# vme_can_vme_1.net
KiCad netlist of a schematic drawn in Altium Designer
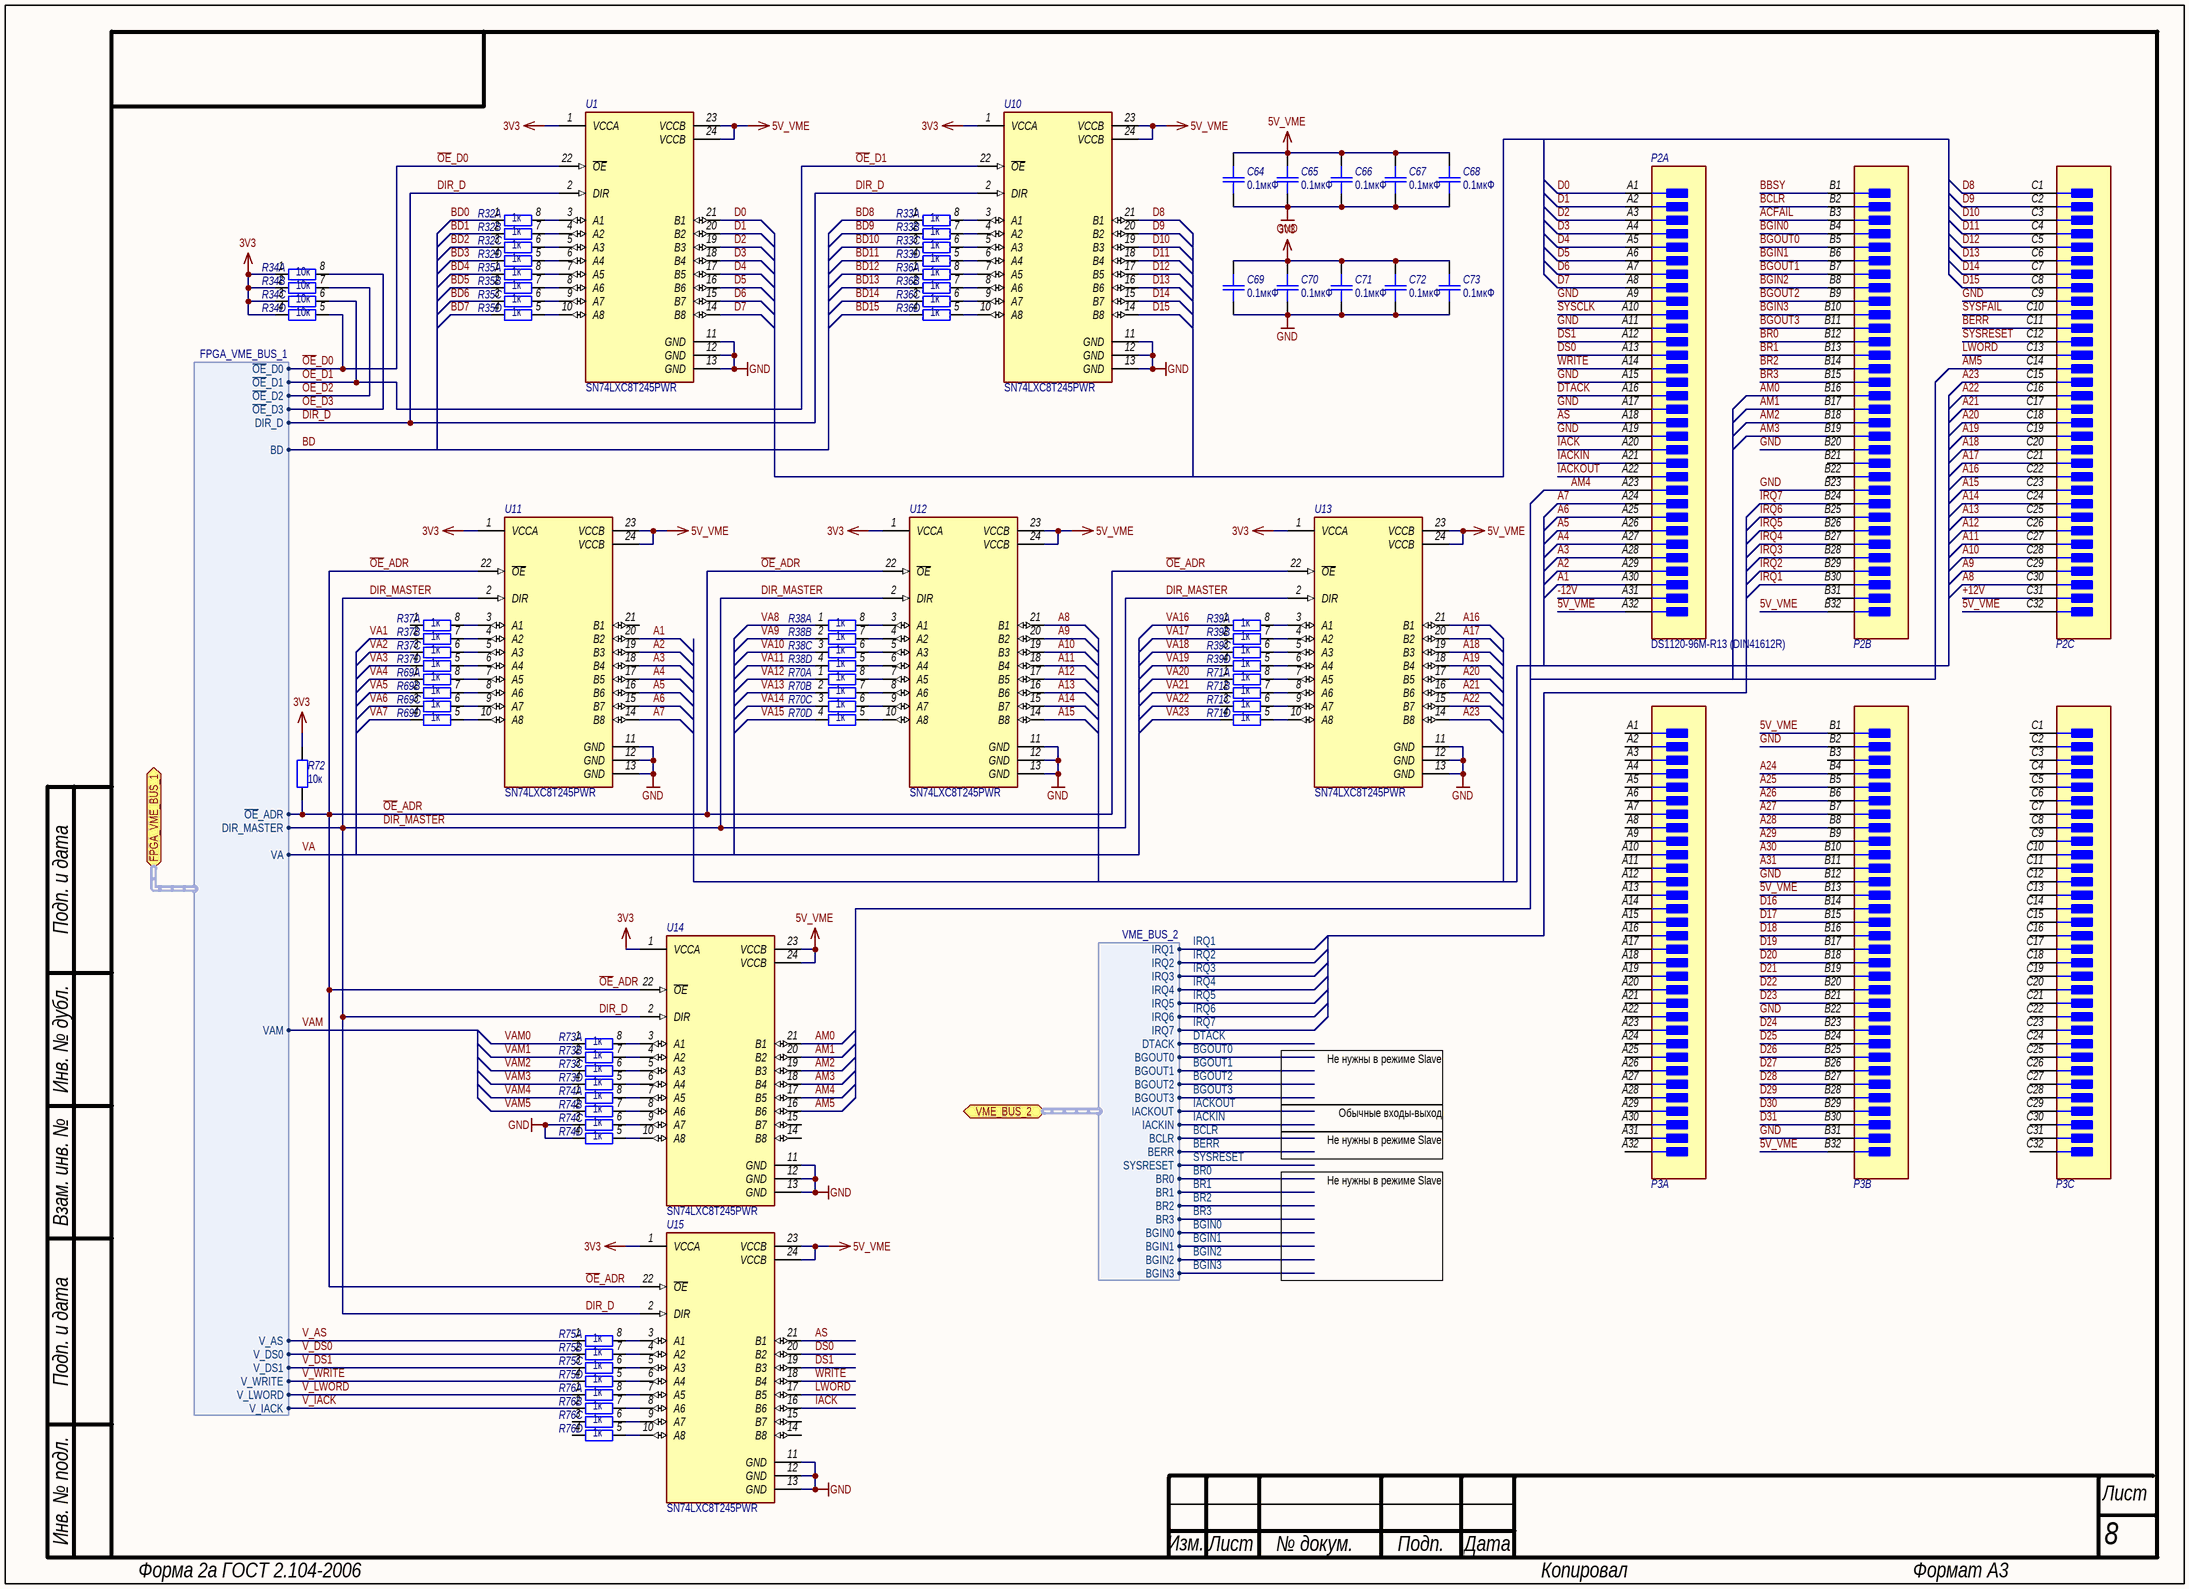
[diagram p0: vme_can_vme_1.SchDoc]

(export (version "E")
  (design (tool "Eeschema 10.0.6"))
  (components
    (comp (ref "C64")
      (value "0.1мкФ")
      (footprint "SMD_C0805")
      (description "Capacitor")
      (libsource (lib "Passive") (part "Capacitor"))
    )
    (comp (ref "C65")
      (value "0.1мкФ")
      (footprint "SMD_C0805")
      (description "Capacitor")
      (libsource (lib "Passive") (part "Capacitor"))
    )
    (comp (ref "C66")
      (value "0.1мкФ")
      (footprint "SMD_C0805")
      (description "Capacitor")
      (libsource (lib "Passive") (part "Capacitor"))
    )
    (comp (ref "C67")
      (value "0.1мкФ")
      (footprint "SMD_C0805")
      (description "Capacitor")
      (libsource (lib "Passive") (part "Capacitor"))
    )
    (comp (ref "C68")
      (value "0.1мкФ")
      (footprint "SMD_C0805")
      (description "Capacitor")
      (libsource (lib "Passive") (part "Capacitor"))
    )
    (comp (ref "C69")
      (value "0.1мкФ")
      (footprint "SMD_C0805")
      (description "Capacitor")
      (libsource (lib "Passive") (part "Capacitor"))
    )
    (comp (ref "C70")
      (value "0.1мкФ")
      (footprint "SMD_C0805")
      (description "Capacitor")
      (libsource (lib "Passive") (part "Capacitor"))
    )
    (comp (ref "C71")
      (value "0.1мкФ")
      (footprint "SMD_C0805")
      (description "Capacitor")
      (libsource (lib "Passive") (part "Capacitor"))
    )
    (comp (ref "C72")
      (value "0.1мкФ")
      (footprint "SMD_C0805")
      (description "Capacitor")
      (libsource (lib "Passive") (part "Capacitor"))
    )
    (comp (ref "C73")
      (value "0.1мкФ")
      (footprint "SMD_C0805")
      (description "Capacitor")
      (libsource (lib "Passive") (part "Capacitor"))
    )
    (comp (ref "P2")
      (value "DS1120-96M-R13 (DIN41612R)")
      (footprint "DS1120-96M-R13")
      (description "Conn Backplane PL 96 POS 2.54mm Solder RA Thru-Hole Box")
      (fields
        (field (name "MANUFACTURER") "TE")
        (field (name "OCTOPART") "https://octopart.com/5650473-5-te+connectivity-39687507")
        (field (name "НАИМЕНОВАНИЕ") "DS1120-96M-R13 (DIN41612R)")
      )
      (libsource (lib "Connector") (part "DS1120-96M-R13"))
    )
    (comp (ref "P3")
      (value "DS1120-96M-R13 (DIN41612R)")
      (footprint "DS1120-96M-R13")
      (description "Conn Backplane PL 96 POS 2.54mm Solder RA Thru-Hole Box")
      (fields
        (field (name "MANUFACTURER") "TE")
        (field (name "OCTOPART") "https://octopart.com/5650473-5-te+connectivity-39687507")
      )
      (libsource (lib "Connector") (part "DS1120-96M-R13"))
    )
    (comp (ref "R32")
      (value "1к")
      (footprint "TC124")
      (description "4 Chip Resistor Array")
      (libsource (lib "Passive") (part "Resistor-4"))
    )
    (comp (ref "R33")
      (value "1к")
      (footprint "TC124")
      (description "4 Chip Resistor Array")
      (libsource (lib "Passive") (part "Resistor-4"))
    )
    (comp (ref "R34")
      (value "10к")
      (footprint "TC124")
      (description "4 Chip Resistor Array")
      (libsource (lib "Passive") (part "Resistor-4"))
    )
    (comp (ref "R35")
      (value "1к")
      (footprint "TC124")
      (description "4 Chip Resistor Array")
      (libsource (lib "Passive") (part "Resistor-4"))
    )
    (comp (ref "R36")
      (value "1к")
      (footprint "TC124")
      (description "4 Chip Resistor Array")
      (libsource (lib "Passive") (part "Resistor-4"))
    )
    (comp (ref "R37")
      (value "1к")
      (footprint "TC124")
      (description "4 Chip Resistor Array")
      (libsource (lib "Passive") (part "Resistor-4"))
    )
    (comp (ref "R38")
      (value "1к")
      (footprint "TC124")
      (description "4 Chip Resistor Array")
      (libsource (lib "Passive") (part "Resistor-4"))
    )
    (comp (ref "R39")
      (value "1к")
      (footprint "TC124")
      (description "4 Chip Resistor Array")
      (libsource (lib "Passive") (part "Resistor-4"))
    )
    (comp (ref "R69")
      (value "1к")
      (footprint "TC124")
      (description "4 Chip Resistor Array")
      (libsource (lib "Passive") (part "Resistor-4"))
    )
    (comp (ref "R70")
      (value "1к")
      (footprint "TC124")
      (description "4 Chip Resistor Array")
      (libsource (lib "Passive") (part "Resistor-4"))
    )
    (comp (ref "R71")
      (value "1к")
      (footprint "TC124")
      (description "4 Chip Resistor Array")
      (libsource (lib "Passive") (part "Resistor-4"))
    )
    (comp (ref "R72")
      (value "10к")
      (footprint "SMD_0805")
      (description "Resistor")
      (libsource (lib "Passive") (part "Resistor"))
    )
    (comp (ref "R73")
      (value "1к")
      (footprint "TC124")
      (description "4 Chip Resistor Array")
      (libsource (lib "Passive") (part "Resistor-4"))
    )
    (comp (ref "R74")
      (value "1к")
      (footprint "TC124")
      (description "4 Chip Resistor Array")
      (libsource (lib "Passive") (part "Resistor-4"))
    )
    (comp (ref "R75")
      (value "1к")
      (footprint "TC124")
      (description "4 Chip Resistor Array")
      (libsource (lib "Passive") (part "Resistor-4"))
    )
    (comp (ref "R76")
      (value "1к")
      (footprint "TC124")
      (description "4 Chip Resistor Array")
      (libsource (lib "Passive") (part "Resistor-4"))
    )
    (comp (ref "U1")
      (value "SN74LXC8T245PWR")
      (footprint "TSSOP-24")
      (description "Dual-Supply Bus Transceiver with Configurable Level Shifting\r\nand 3-State Outputs")
      (fields (field (name "НАИМЕНОВАНИЕ") "SN74LXC8T245PWR"))
      (libsource (lib "Transceiver") (part "SN74LXC8T245PWR"))
    )
    (comp (ref "U10")
      (value "SN74LXC8T245PWR")
      (footprint "TSSOP-24")
      (description "Dual-Supply Bus Transceiver with Configurable Level Shifting\r\nand 3-State Outputs")
      (fields (field (name "НАИМЕНОВАНИЕ") "SN74LXC8T245PWR"))
      (libsource (lib "Transceiver") (part "SN74LXC8T245PWR"))
    )
    (comp (ref "U11")
      (value "SN74LXC8T245PWR")
      (footprint "TSSOP-24")
      (description "Dual-Supply Bus Transceiver with Configurable Level Shifting\r\nand 3-State Outputs")
      (fields (field (name "НАИМЕНОВАНИЕ") "SN74LXC8T245PWR"))
      (libsource (lib "Transceiver") (part "SN74LXC8T245PWR"))
    )
    (comp (ref "U12")
      (value "SN74LXC8T245PWR")
      (footprint "TSSOP-24")
      (description "Dual-Supply Bus Transceiver with Configurable Level Shifting\r\nand 3-State Outputs")
      (fields (field (name "НАИМЕНОВАНИЕ") "SN74LXC8T245PWR"))
      (libsource (lib "Transceiver") (part "SN74LXC8T245PWR"))
    )
    (comp (ref "U13")
      (value "SN74LXC8T245PWR")
      (footprint "TSSOP-24")
      (description "Dual-Supply Bus Transceiver with Configurable Level Shifting\r\nand 3-State Outputs")
      (fields (field (name "НАИМЕНОВАНИЕ") "SN74LXC8T245PWR"))
      (libsource (lib "Transceiver") (part "SN74LXC8T245PWR"))
    )
    (comp (ref "U14")
      (value "SN74LXC8T245PWR")
      (footprint "TSSOP-24")
      (description "Dual-Supply Bus Transceiver with Configurable Level Shifting\r\nand 3-State Outputs")
      (fields (field (name "НАИМЕНОВАНИЕ") "SN74LXC8T245PWR"))
      (libsource (lib "Transceiver") (part "SN74LXC8T245PWR"))
    )
    (comp (ref "U15")
      (value "SN74LXC8T245PWR")
      (footprint "TSSOP-24")
      (description "Dual-Supply Bus Transceiver with Configurable Level Shifting\r\nand 3-State Outputs")
      (fields (field (name "НАИМЕНОВАНИЕ") "SN74LXC8T245PWR"))
      (libsource (lib "Transceiver") (part "SN74LXC8T245PWR"))
    )
  )
  (nets
    (net (code "6") (name "/+12V") (class "Default")
      (node (ref "P2") (pin "C31") (pinfunction "C31_C31") (pintype "passive"))
    )
    (net (code "7") (name "/-12V") (class "Default")
      (node (ref "P2") (pin "A31") (pinfunction "A31_A31") (pintype "passive"))
    )
    (net (code "8") (name "/A1") (class "Default")
      (node (ref "P2") (pin "A30") (pinfunction "A30_A30") (pintype "passive"))
      (node (ref "U11") (pin "20") (pinfunction "B2_20") (pintype "bidirectional"))
    )
    (net (code "9") (name "/A2") (class "Default")
      (node (ref "P2") (pin "A29") (pinfunction "A29_A29") (pintype "passive"))
      (node (ref "U11") (pin "19") (pinfunction "B3_19") (pintype "bidirectional"))
    )
    (net (code "10") (name "/A3") (class "Default")
      (node (ref "P2") (pin "A28") (pinfunction "A28_A28") (pintype "passive"))
      (node (ref "U11") (pin "18") (pinfunction "B4_18") (pintype "bidirectional"))
    )
    (net (code "11") (name "/A4") (class "Default")
      (node (ref "P2") (pin "A27") (pinfunction "A27_A27") (pintype "passive"))
      (node (ref "U11") (pin "17") (pinfunction "B5_17") (pintype "bidirectional"))
    )
    (net (code "12") (name "/A5") (class "Default")
      (node (ref "P2") (pin "A26") (pinfunction "A26_A26") (pintype "passive"))
      (node (ref "U11") (pin "16") (pinfunction "B6_16") (pintype "bidirectional"))
    )
    (net (code "13") (name "/A6") (class "Default")
      (node (ref "P2") (pin "A25") (pinfunction "A25_A25") (pintype "passive"))
      (node (ref "U11") (pin "15") (pinfunction "B7_15") (pintype "bidirectional"))
    )
    (net (code "14") (name "/A7") (class "Default")
      (node (ref "P2") (pin "A24") (pinfunction "A24_A24") (pintype "passive"))
      (node (ref "U11") (pin "14") (pinfunction "B8_14") (pintype "bidirectional"))
    )
    (net (code "15") (name "/A8") (class "Default")
      (node (ref "P2") (pin "C30") (pinfunction "C30_C30") (pintype "passive"))
      (node (ref "U12") (pin "21") (pinfunction "B1_21") (pintype "bidirectional"))
    )
    (net (code "16") (name "/A9") (class "Default")
      (node (ref "P2") (pin "C29") (pinfunction "C29_C29") (pintype "passive"))
      (node (ref "U12") (pin "20") (pinfunction "B2_20") (pintype "bidirectional"))
    )
    (net (code "17") (name "/A10") (class "Default")
      (node (ref "P2") (pin "C28") (pinfunction "C28_C28") (pintype "passive"))
      (node (ref "U12") (pin "19") (pinfunction "B3_19") (pintype "bidirectional"))
    )
    (net (code "18") (name "/A11") (class "Default")
      (node (ref "P2") (pin "C27") (pinfunction "C27_C27") (pintype "passive"))
      (node (ref "U12") (pin "18") (pinfunction "B4_18") (pintype "bidirectional"))
    )
    (net (code "19") (name "/A12") (class "Default")
      (node (ref "P2") (pin "C26") (pinfunction "C26_C26") (pintype "passive"))
      (node (ref "U12") (pin "17") (pinfunction "B5_17") (pintype "bidirectional"))
    )
    (net (code "20") (name "/A13") (class "Default")
      (node (ref "P2") (pin "C25") (pinfunction "C25_C25") (pintype "passive"))
      (node (ref "U12") (pin "16") (pinfunction "B6_16") (pintype "bidirectional"))
    )
    (net (code "21") (name "/A14") (class "Default")
      (node (ref "P2") (pin "C24") (pinfunction "C24_C24") (pintype "passive"))
      (node (ref "U12") (pin "15") (pinfunction "B7_15") (pintype "bidirectional"))
    )
    (net (code "22") (name "/A15") (class "Default")
      (node (ref "P2") (pin "C23") (pinfunction "C23_C23") (pintype "passive"))
      (node (ref "U12") (pin "14") (pinfunction "B8_14") (pintype "bidirectional"))
    )
    (net (code "23") (name "/A16") (class "Default")
      (node (ref "P2") (pin "C22") (pinfunction "C22_C22") (pintype "passive"))
      (node (ref "U13") (pin "21") (pinfunction "B1_21") (pintype "bidirectional"))
    )
    (net (code "24") (name "/A17") (class "Default")
      (node (ref "P2") (pin "C21") (pinfunction "C21_C21") (pintype "passive"))
      (node (ref "U13") (pin "20") (pinfunction "B2_20") (pintype "bidirectional"))
    )
    (net (code "25") (name "/A18") (class "Default")
      (node (ref "P2") (pin "C20") (pinfunction "C20_C20") (pintype "passive"))
      (node (ref "U13") (pin "19") (pinfunction "B3_19") (pintype "bidirectional"))
    )
    (net (code "26") (name "/A19") (class "Default")
      (node (ref "P2") (pin "C19") (pinfunction "C19_C19") (pintype "passive"))
      (node (ref "U13") (pin "18") (pinfunction "B4_18") (pintype "bidirectional"))
    )
    (net (code "27") (name "/A20") (class "Default")
      (node (ref "P2") (pin "C18") (pinfunction "C18_C18") (pintype "passive"))
      (node (ref "U13") (pin "17") (pinfunction "B5_17") (pintype "bidirectional"))
    )
    (net (code "28") (name "/A21") (class "Default")
      (node (ref "P2") (pin "C17") (pinfunction "C17_C17") (pintype "passive"))
      (node (ref "U13") (pin "16") (pinfunction "B6_16") (pintype "bidirectional"))
    )
    (net (code "29") (name "/A22") (class "Default")
      (node (ref "P2") (pin "C16") (pinfunction "C16_C16") (pintype "passive"))
      (node (ref "U13") (pin "15") (pinfunction "B7_15") (pintype "bidirectional"))
    )
    (net (code "30") (name "/A23") (class "Default")
      (node (ref "P2") (pin "C15") (pinfunction "C15_C15") (pintype "passive"))
      (node (ref "U13") (pin "14") (pinfunction "B8_14") (pintype "bidirectional"))
    )
    (net (code "31") (name "/A24") (class "Default")
      (node (ref "P3") (pin "B4") (pinfunction "B4_B4") (pintype "passive"))
    )
    (net (code "32") (name "/A25") (class "Default")
      (node (ref "P3") (pin "B5") (pinfunction "B5_B5") (pintype "passive"))
    )
    (net (code "33") (name "/A26") (class "Default")
      (node (ref "P3") (pin "B6") (pinfunction "B6_B6") (pintype "passive"))
    )
    (net (code "34") (name "/A27") (class "Default")
      (node (ref "P3") (pin "B7") (pinfunction "B7_B7") (pintype "passive"))
    )
    (net (code "35") (name "/A28") (class "Default")
      (node (ref "P3") (pin "B8") (pinfunction "B8_B8") (pintype "passive"))
    )
    (net (code "36") (name "/A29") (class "Default")
      (node (ref "P3") (pin "B9") (pinfunction "B9_B9") (pintype "passive"))
    )
    (net (code "37") (name "/A30") (class "Default")
      (node (ref "P3") (pin "B10") (pinfunction "B10_B10") (pintype "passive"))
    )
    (net (code "38") (name "/A31") (class "Default")
      (node (ref "P3") (pin "B11") (pinfunction "B11_B11") (pintype "passive"))
    )
    (net (code "39") (name "/ACFAIL") (class "Default")
      (node (ref "P2") (pin "B3") (pinfunction "B3_B3") (pintype "passive"))
    )
    (net (code "40") (name "/AM0") (class "Default")
      (node (ref "P2") (pin "B16") (pinfunction "B16_B16") (pintype "passive"))
      (node (ref "U14") (pin "21") (pinfunction "B1_21") (pintype "bidirectional"))
    )
    (net (code "41") (name "/AM1") (class "Default")
      (node (ref "P2") (pin "B17") (pinfunction "B17_B17") (pintype "passive"))
      (node (ref "U14") (pin "20") (pinfunction "B2_20") (pintype "bidirectional"))
    )
    (net (code "42") (name "/AM2") (class "Default")
      (node (ref "P2") (pin "B18") (pinfunction "B18_B18") (pintype "passive"))
      (node (ref "U14") (pin "19") (pinfunction "B3_19") (pintype "bidirectional"))
    )
    (net (code "43") (name "/AM3") (class "Default")
      (node (ref "P2") (pin "B19") (pinfunction "B19_B19") (pintype "passive"))
      (node (ref "U14") (pin "18") (pinfunction "B4_18") (pintype "bidirectional"))
    )
    (net (code "44") (name "/AM4") (class "Default")
      (node (ref "P2") (pin "A23") (pinfunction "A23_A23") (pintype "passive"))
      (node (ref "U14") (pin "17") (pinfunction "B5_17") (pintype "bidirectional"))
    )
    (net (code "45") (name "/AM5") (class "Default")
      (node (ref "P2") (pin "C14") (pinfunction "C14_C14") (pintype "passive"))
      (node (ref "U14") (pin "16") (pinfunction "B6_16") (pintype "bidirectional"))
    )
    (net (code "46") (name "/AS") (class "Default")
      (node (ref "P2") (pin "A18") (pinfunction "A18_A18") (pintype "passive"))
      (node (ref "U15") (pin "21") (pinfunction "B1_21") (pintype "bidirectional"))
    )
    (net (code "47") (name "/BBSY") (class "Default")
      (node (ref "P2") (pin "B1") (pinfunction "B1_B1") (pintype "passive"))
    )
    (net (code "48") (name "/BCLR") (class "Default")
      (node (ref "P2") (pin "B2") (pinfunction "B2_B2") (pintype "passive"))
    )
    (net (code "49") (name "/BD0") (class "Default")
      (node (ref "R32") (pin "1") (pinfunction "1_1") (pintype "passive"))
    )
    (net (code "50") (name "/BD1") (class "Default")
      (node (ref "R32") (pin "2") (pinfunction "2_2") (pintype "passive"))
    )
    (net (code "51") (name "/BD2") (class "Default")
      (node (ref "R32") (pin "3") (pinfunction "3_3") (pintype "passive"))
    )
    (net (code "52") (name "/BD3") (class "Default")
      (node (ref "R32") (pin "4") (pinfunction "4_4") (pintype "passive"))
    )
    (net (code "53") (name "/BD4") (class "Default")
      (node (ref "R35") (pin "1") (pinfunction "1_1") (pintype "passive"))
    )
    (net (code "54") (name "/BD5") (class "Default")
      (node (ref "R35") (pin "2") (pinfunction "2_2") (pintype "passive"))
    )
    (net (code "55") (name "/BD6") (class "Default")
      (node (ref "R35") (pin "3") (pinfunction "3_3") (pintype "passive"))
    )
    (net (code "56") (name "/BD7") (class "Default")
      (node (ref "R35") (pin "4") (pinfunction "4_4") (pintype "passive"))
    )
    (net (code "57") (name "/BD8") (class "Default")
      (node (ref "R33") (pin "1") (pinfunction "1_1") (pintype "passive"))
    )
    (net (code "58") (name "/BD9") (class "Default")
      (node (ref "R33") (pin "2") (pinfunction "2_2") (pintype "passive"))
    )
    (net (code "59") (name "/BD10") (class "Default")
      (node (ref "R33") (pin "3") (pinfunction "3_3") (pintype "passive"))
    )
    (net (code "60") (name "/BD11") (class "Default")
      (node (ref "R33") (pin "4") (pinfunction "4_4") (pintype "passive"))
    )
    (net (code "61") (name "/BD12") (class "Default")
      (node (ref "R36") (pin "1") (pinfunction "1_1") (pintype "passive"))
    )
    (net (code "62") (name "/BD13") (class "Default")
      (node (ref "R36") (pin "2") (pinfunction "2_2") (pintype "passive"))
    )
    (net (code "63") (name "/BD14") (class "Default")
      (node (ref "R36") (pin "3") (pinfunction "3_3") (pintype "passive"))
    )
    (net (code "64") (name "/BD15") (class "Default")
      (node (ref "R36") (pin "4") (pinfunction "4_4") (pintype "passive"))
    )
    (net (code "65") (name "/BERR") (class "Default")
      (node (ref "P2") (pin "C11") (pinfunction "C11_C11") (pintype "passive"))
    )
    (net (code "66") (name "/BGIN0") (class "Default")
      (node (ref "P2") (pin "B4") (pinfunction "B4_B4") (pintype "passive"))
    )
    (net (code "67") (name "/BGIN1") (class "Default")
      (node (ref "P2") (pin "B6") (pinfunction "B6_B6") (pintype "passive"))
    )
    (net (code "68") (name "/BGIN2") (class "Default")
      (node (ref "P2") (pin "B8") (pinfunction "B8_B8") (pintype "passive"))
    )
    (net (code "69") (name "/BGIN3") (class "Default")
      (node (ref "P2") (pin "B10") (pinfunction "B10_B10") (pintype "passive"))
    )
    (net (code "70") (name "/BGOUT0") (class "Default")
      (node (ref "P2") (pin "B5") (pinfunction "B5_B5") (pintype "passive"))
    )
    (net (code "71") (name "/BGOUT1") (class "Default")
      (node (ref "P2") (pin "B7") (pinfunction "B7_B7") (pintype "passive"))
    )
    (net (code "72") (name "/BGOUT2") (class "Default")
      (node (ref "P2") (pin "B9") (pinfunction "B9_B9") (pintype "passive"))
    )
    (net (code "73") (name "/BGOUT3") (class "Default")
      (node (ref "P2") (pin "B11") (pinfunction "B11_B11") (pintype "passive"))
    )
    (net (code "74") (name "/BR0") (class "Default")
      (node (ref "P2") (pin "B12") (pinfunction "B12_B12") (pintype "passive"))
    )
    (net (code "75") (name "/BR1") (class "Default")
      (node (ref "P2") (pin "B13") (pinfunction "B13_B13") (pintype "passive"))
    )
    (net (code "76") (name "/BR2") (class "Default")
      (node (ref "P2") (pin "B14") (pinfunction "B14_B14") (pintype "passive"))
    )
    (net (code "77") (name "/BR3") (class "Default")
      (node (ref "P2") (pin "B15") (pinfunction "B15_B15") (pintype "passive"))
    )
    (net (code "78") (name "/D0") (class "Default")
      (node (ref "P2") (pin "A1") (pinfunction "A1_A1") (pintype "passive"))
      (node (ref "U1") (pin "21") (pinfunction "B1_21") (pintype "bidirectional"))
    )
    (net (code "79") (name "/D1") (class "Default")
      (node (ref "P2") (pin "A2") (pinfunction "A2_A2") (pintype "passive"))
      (node (ref "U1") (pin "20") (pinfunction "B2_20") (pintype "bidirectional"))
    )
    (net (code "80") (name "/D2") (class "Default")
      (node (ref "P2") (pin "A3") (pinfunction "A3_A3") (pintype "passive"))
      (node (ref "U1") (pin "19") (pinfunction "B3_19") (pintype "bidirectional"))
    )
    (net (code "81") (name "/D3") (class "Default")
      (node (ref "P2") (pin "A4") (pinfunction "A4_A4") (pintype "passive"))
      (node (ref "U1") (pin "18") (pinfunction "B4_18") (pintype "bidirectional"))
    )
    (net (code "82") (name "/D4") (class "Default")
      (node (ref "P2") (pin "A5") (pinfunction "A5_A5") (pintype "passive"))
      (node (ref "U1") (pin "17") (pinfunction "B5_17") (pintype "bidirectional"))
    )
    (net (code "83") (name "/D5") (class "Default")
      (node (ref "P2") (pin "A6") (pinfunction "A6_A6") (pintype "passive"))
      (node (ref "U1") (pin "16") (pinfunction "B6_16") (pintype "bidirectional"))
    )
    (net (code "84") (name "/D6") (class "Default")
      (node (ref "P2") (pin "A7") (pinfunction "A7_A7") (pintype "passive"))
      (node (ref "U1") (pin "15") (pinfunction "B7_15") (pintype "bidirectional"))
    )
    (net (code "85") (name "/D7") (class "Default")
      (node (ref "P2") (pin "A8") (pinfunction "A8_A8") (pintype "passive"))
      (node (ref "U1") (pin "14") (pinfunction "B8_14") (pintype "bidirectional"))
    )
    (net (code "86") (name "/D8") (class "Default")
      (node (ref "P2") (pin "C1") (pinfunction "C1_C1") (pintype "passive"))
      (node (ref "U10") (pin "21") (pinfunction "B1_21") (pintype "bidirectional"))
    )
    (net (code "87") (name "/D9") (class "Default")
      (node (ref "P2") (pin "C2") (pinfunction "C2_C2") (pintype "passive"))
      (node (ref "U10") (pin "20") (pinfunction "B2_20") (pintype "bidirectional"))
    )
    (net (code "88") (name "/D10") (class "Default")
      (node (ref "P2") (pin "C3") (pinfunction "C3_C3") (pintype "passive"))
      (node (ref "U10") (pin "19") (pinfunction "B3_19") (pintype "bidirectional"))
    )
    (net (code "89") (name "/D11") (class "Default")
      (node (ref "P2") (pin "C4") (pinfunction "C4_C4") (pintype "passive"))
      (node (ref "U10") (pin "18") (pinfunction "B4_18") (pintype "bidirectional"))
    )
    (net (code "90") (name "/D12") (class "Default")
      (node (ref "P2") (pin "C5") (pinfunction "C5_C5") (pintype "passive"))
      (node (ref "U10") (pin "17") (pinfunction "B5_17") (pintype "bidirectional"))
    )
    (net (code "91") (name "/D13") (class "Default")
      (node (ref "P2") (pin "C6") (pinfunction "C6_C6") (pintype "passive"))
      (node (ref "U10") (pin "16") (pinfunction "B6_16") (pintype "bidirectional"))
    )
    (net (code "92") (name "/D14") (class "Default")
      (node (ref "P2") (pin "C7") (pinfunction "C7_C7") (pintype "passive"))
      (node (ref "U10") (pin "15") (pinfunction "B7_15") (pintype "bidirectional"))
    )
    (net (code "93") (name "/D15") (class "Default")
      (node (ref "P2") (pin "C8") (pinfunction "C8_C8") (pintype "passive"))
      (node (ref "U10") (pin "14") (pinfunction "B8_14") (pintype "bidirectional"))
    )
    (net (code "94") (name "/D16") (class "Default")
      (node (ref "P3") (pin "B14") (pinfunction "B14_B14") (pintype "passive"))
    )
    (net (code "95") (name "/D17") (class "Default")
      (node (ref "P3") (pin "B15") (pinfunction "B15_B15") (pintype "passive"))
    )
    (net (code "96") (name "/D18") (class "Default")
      (node (ref "P3") (pin "B16") (pinfunction "B16_B16") (pintype "passive"))
    )
    (net (code "97") (name "/D19") (class "Default")
      (node (ref "P3") (pin "B17") (pinfunction "B17_B17") (pintype "passive"))
    )
    (net (code "98") (name "/D20") (class "Default")
      (node (ref "P3") (pin "B18") (pinfunction "B18_B18") (pintype "passive"))
    )
    (net (code "99") (name "/D21") (class "Default")
      (node (ref "P3") (pin "B19") (pinfunction "B19_B19") (pintype "passive"))
    )
    (net (code "100") (name "/D22") (class "Default")
      (node (ref "P3") (pin "B20") (pinfunction "B20_B20") (pintype "passive"))
    )
    (net (code "101") (name "/D23") (class "Default")
      (node (ref "P3") (pin "B21") (pinfunction "B21_B21") (pintype "passive"))
    )
    (net (code "102") (name "/D24") (class "Default")
      (node (ref "P3") (pin "B23") (pinfunction "B23_B23") (pintype "passive"))
    )
    (net (code "103") (name "/D25") (class "Default")
      (node (ref "P3") (pin "B24") (pinfunction "B24_B24") (pintype "passive"))
    )
    (net (code "104") (name "/D26") (class "Default")
      (node (ref "P3") (pin "B25") (pinfunction "B25_B25") (pintype "passive"))
    )
    (net (code "105") (name "/D27") (class "Default")
      (node (ref "P3") (pin "B26") (pinfunction "B26_B26") (pintype "passive"))
    )
    (net (code "106") (name "/D28") (class "Default")
      (node (ref "P3") (pin "B27") (pinfunction "B27_B27") (pintype "passive"))
    )
    (net (code "107") (name "/D29") (class "Default")
      (node (ref "P3") (pin "B28") (pinfunction "B28_B28") (pintype "passive"))
    )
    (net (code "108") (name "/D30") (class "Default")
      (node (ref "P3") (pin "B29") (pinfunction "B29_B29") (pintype "passive"))
    )
    (net (code "109") (name "/D31") (class "Default")
      (node (ref "P3") (pin "B30") (pinfunction "B30_B30") (pintype "passive"))
    )
    (net (code "110") (name "/DIR_D") (class "Default")
      (node (ref "U1") (pin "2") (pinfunction "DIR_2") (pintype "input"))
      (node (ref "U10") (pin "2") (pinfunction "DIR_2") (pintype "input"))
      (node (ref "U11") (pin "2") (pinfunction "DIR_2") (pintype "input"))
      (node (ref "U12") (pin "2") (pinfunction "DIR_2") (pintype "input"))
      (node (ref "U13") (pin "2") (pinfunction "DIR_2") (pintype "input"))
      (node (ref "U14") (pin "2") (pinfunction "DIR_2") (pintype "input"))
      (node (ref "U15") (pin "2") (pinfunction "DIR_2") (pintype "input"))
    )
    (net (code "111") (name "/DS0") (class "Default")
      (node (ref "P2") (pin "A13") (pinfunction "A13_A13") (pintype "passive"))
      (node (ref "U15") (pin "20") (pinfunction "B2_20") (pintype "bidirectional"))
    )
    (net (code "112") (name "/DS1") (class "Default")
      (node (ref "P2") (pin "A12") (pinfunction "A12_A12") (pintype "passive"))
      (node (ref "U15") (pin "19") (pinfunction "B3_19") (pintype "bidirectional"))
    )
    (net (code "113") (name "/DTACK") (class "Default")
      (node (ref "P2") (pin "A16") (pinfunction "A16_A16") (pintype "passive"))
    )
    (net (code "115") (name "/IACK") (class "Default")
      (node (ref "P2") (pin "A20") (pinfunction "A20_A20") (pintype "passive"))
      (node (ref "U15") (pin "16") (pinfunction "B6_16") (pintype "bidirectional"))
    )
    (net (code "116") (name "/IACKIN") (class "Default")
      (node (ref "P2") (pin "A21") (pinfunction "A21_A21") (pintype "passive"))
    )
    (net (code "117") (name "/IACKOUT") (class "Default")
      (node (ref "P2") (pin "A22") (pinfunction "A22_A22") (pintype "passive"))
    )
    (net (code "118") (name "/IRQ1") (class "Default")
      (node (ref "P2") (pin "B30") (pinfunction "B30_B30") (pintype "passive"))
    )
    (net (code "119") (name "/IRQ2") (class "Default")
      (node (ref "P2") (pin "B29") (pinfunction "B29_B29") (pintype "passive"))
    )
    (net (code "120") (name "/IRQ3") (class "Default")
      (node (ref "P2") (pin "B28") (pinfunction "B28_B28") (pintype "passive"))
    )
    (net (code "121") (name "/IRQ4") (class "Default")
      (node (ref "P2") (pin "B27") (pinfunction "B27_B27") (pintype "passive"))
    )
    (net (code "122") (name "/IRQ5") (class "Default")
      (node (ref "P2") (pin "B26") (pinfunction "B26_B26") (pintype "passive"))
    )
    (net (code "123") (name "/IRQ6") (class "Default")
      (node (ref "P2") (pin "B25") (pinfunction "B25_B25") (pintype "passive"))
    )
    (net (code "124") (name "/IRQ7") (class "Default")
      (node (ref "P2") (pin "B24") (pinfunction "B24_B24") (pintype "passive"))
    )
    (net (code "125") (name "/LWORD") (class "Default")
      (node (ref "P2") (pin "C13") (pinfunction "C13_C13") (pintype "passive"))
      (node (ref "U15") (pin "17") (pinfunction "B5_17") (pintype "bidirectional"))
    )
    (net (code "126") (name "/SYSCLK") (class "Default")
      (node (ref "P2") (pin "A10") (pinfunction "A10_A10") (pintype "passive"))
    )
    (net (code "127") (name "/SYSFAIL") (class "Default")
      (node (ref "P2") (pin "C10") (pinfunction "C10_C10") (pintype "passive"))
    )
    (net (code "128") (name "/SYSRESET") (class "Default")
      (node (ref "P2") (pin "C12") (pinfunction "C12_C12") (pintype "passive"))
    )
    (net (code "129") (name "/VA1") (class "Default")
      (node (ref "R37") (pin "2") (pinfunction "2_2") (pintype "passive"))
    )
    (net (code "130") (name "/VA2") (class "Default")
      (node (ref "R37") (pin "3") (pinfunction "3_3") (pintype "passive"))
    )
    (net (code "131") (name "/VA3") (class "Default")
      (node (ref "R37") (pin "4") (pinfunction "4_4") (pintype "passive"))
    )
    (net (code "132") (name "/VA4") (class "Default")
      (node (ref "R69") (pin "1") (pinfunction "1_1") (pintype "passive"))
    )
    (net (code "133") (name "/VA5") (class "Default")
      (node (ref "R69") (pin "2") (pinfunction "2_2") (pintype "passive"))
    )
    (net (code "134") (name "/VA6") (class "Default")
      (node (ref "R69") (pin "3") (pinfunction "3_3") (pintype "passive"))
    )
    (net (code "135") (name "/VA7") (class "Default")
      (node (ref "R69") (pin "4") (pinfunction "4_4") (pintype "passive"))
    )
    (net (code "136") (name "/VA8") (class "Default")
      (node (ref "R38") (pin "1") (pinfunction "1_1") (pintype "passive"))
    )
    (net (code "137") (name "/VA9") (class "Default")
      (node (ref "R38") (pin "2") (pinfunction "2_2") (pintype "passive"))
    )
    (net (code "138") (name "/VA10") (class "Default")
      (node (ref "R38") (pin "3") (pinfunction "3_3") (pintype "passive"))
    )
    (net (code "139") (name "/VA11") (class "Default")
      (node (ref "R38") (pin "4") (pinfunction "4_4") (pintype "passive"))
    )
    (net (code "140") (name "/VA12") (class "Default")
      (node (ref "R70") (pin "1") (pinfunction "1_1") (pintype "passive"))
    )
    (net (code "141") (name "/VA13") (class "Default")
      (node (ref "R70") (pin "2") (pinfunction "2_2") (pintype "passive"))
    )
    (net (code "142") (name "/VA14") (class "Default")
      (node (ref "R70") (pin "3") (pinfunction "3_3") (pintype "passive"))
    )
    (net (code "143") (name "/VA15") (class "Default")
      (node (ref "R70") (pin "4") (pinfunction "4_4") (pintype "passive"))
    )
    (net (code "144") (name "/VA16") (class "Default")
      (node (ref "R39") (pin "1") (pinfunction "1_1") (pintype "passive"))
    )
    (net (code "145") (name "/VA17") (class "Default")
      (node (ref "R39") (pin "2") (pinfunction "2_2") (pintype "passive"))
    )
    (net (code "146") (name "/VA18") (class "Default")
      (node (ref "R39") (pin "3") (pinfunction "3_3") (pintype "passive"))
    )
    (net (code "147") (name "/VA19") (class "Default")
      (node (ref "R39") (pin "4") (pinfunction "4_4") (pintype "passive"))
    )
    (net (code "148") (name "/VA20") (class "Default")
      (node (ref "R71") (pin "1") (pinfunction "1_1") (pintype "passive"))
    )
    (net (code "149") (name "/VA21") (class "Default")
      (node (ref "R71") (pin "2") (pinfunction "2_2") (pintype "passive"))
    )
    (net (code "150") (name "/VA22") (class "Default")
      (node (ref "R71") (pin "3") (pinfunction "3_3") (pintype "passive"))
    )
    (net (code "151") (name "/VA23") (class "Default")
      (node (ref "R71") (pin "4") (pinfunction "4_4") (pintype "passive"))
    )
    (net (code "152") (name "/VAM0") (class "Default")
      (node (ref "R73") (pin "1") (pinfunction "1_1") (pintype "passive"))
    )
    (net (code "153") (name "/VAM1") (class "Default")
      (node (ref "R73") (pin "2") (pinfunction "2_2") (pintype "passive"))
    )
    (net (code "154") (name "/VAM2") (class "Default")
      (node (ref "R73") (pin "3") (pinfunction "3_3") (pintype "passive"))
    )
    (net (code "155") (name "/VAM3") (class "Default")
      (node (ref "R73") (pin "4") (pinfunction "4_4") (pintype "passive"))
    )
    (net (code "156") (name "/VAM4") (class "Default")
      (node (ref "R74") (pin "1") (pinfunction "1_1") (pintype "passive"))
    )
    (net (code "157") (name "/VAM5") (class "Default")
      (node (ref "R74") (pin "2") (pinfunction "2_2") (pintype "passive"))
    )
    (net (code "159") (name "/V_AS") (class "Default")
      (node (ref "R75") (pin "1") (pinfunction "1_1") (pintype "passive"))
    )
    (net (code "160") (name "/V_DS0") (class "Default")
      (node (ref "R75") (pin "2") (pinfunction "2_2") (pintype "passive"))
    )
    (net (code "161") (name "/V_DS1") (class "Default")
      (node (ref "R75") (pin "3") (pinfunction "3_3") (pintype "passive"))
    )
    (net (code "162") (name "/V_IACK") (class "Default")
      (node (ref "R76") (pin "2") (pinfunction "2_2") (pintype "passive"))
    )
    (net (code "163") (name "/V_LWORD") (class "Default")
      (node (ref "R76") (pin "1") (pinfunction "1_1") (pintype "passive"))
    )
    (net (code "164") (name "/V_WRITE") (class "Default")
      (node (ref "R75") (pin "4") (pinfunction "4_4") (pintype "passive"))
    )
    (net (code "165") (name "/WRITE") (class "Default")
      (node (ref "P2") (pin "A14") (pinfunction "A14_A14") (pintype "passive"))
      (node (ref "U15") (pin "18") (pinfunction "B4_18") (pintype "bidirectional"))
    )
    (net (code "169") (name "/~{OE}_ADR") (class "Default")
      (node (ref "R72") (pin "1") (pinfunction "1_1") (pintype "passive"))
      (node (ref "U11") (pin "22") (pinfunction "~{OE}_22") (pintype "input"))
      (node (ref "U12") (pin "22") (pinfunction "~{OE}_22") (pintype "input"))
      (node (ref "U13") (pin "22") (pinfunction "~{OE}_22") (pintype "input"))
      (node (ref "U14") (pin "22") (pinfunction "~{OE}_22") (pintype "input"))
      (node (ref "U15") (pin "22") (pinfunction "~{OE}_22") (pintype "input"))
    )
    (net (code "170") (name "/~{OE}_D0") (class "Default")
      (node (ref "R34") (pin "5") (pinfunction "5_5") (pintype "passive"))
      (node (ref "U1") (pin "22") (pinfunction "~{OE}_22") (pintype "input"))
    )
    (net (code "171") (name "/~{OE}_D1") (class "Default")
      (node (ref "R34") (pin "6") (pinfunction "6_6") (pintype "passive"))
      (node (ref "U10") (pin "22") (pinfunction "~{OE}_22") (pintype "input"))
    )
    (net (code "172") (name "/~{OE}_D2") (class "Default")
      (node (ref "R34") (pin "7") (pinfunction "7_7") (pintype "passive"))
    )
    (net (code "173") (name "/~{OE}_D3") (class "Default")
      (node (ref "R34") (pin "8") (pinfunction "8_8") (pintype "passive"))
    )
    (net (code "174") (name "3V3") (class "Default")
      (node (ref "C69") (pin "2") (pinfunction "2_2") (pintype "passive"))
      (node (ref "C70") (pin "2") (pinfunction "2_2") (pintype "passive"))
      (node (ref "C71") (pin "2") (pinfunction "2_2") (pintype "passive"))
      (node (ref "C72") (pin "2") (pinfunction "2_2") (pintype "passive"))
      (node (ref "C73") (pin "2") (pinfunction "2_2") (pintype "passive"))
      (node (ref "R34") (pin "1") (pinfunction "1_1") (pintype "passive"))
      (node (ref "R34") (pin "2") (pinfunction "2_2") (pintype "passive"))
      (node (ref "R34") (pin "3") (pinfunction "3_3") (pintype "passive"))
      (node (ref "R34") (pin "4") (pinfunction "4_4") (pintype "passive"))
      (node (ref "R72") (pin "2") (pinfunction "2_2") (pintype "passive"))
      (node (ref "U1") (pin "1") (pinfunction "VCCA_1") (pintype "power_in"))
      (node (ref "U10") (pin "1") (pinfunction "VCCA_1") (pintype "power_in"))
      (node (ref "U11") (pin "1") (pinfunction "VCCA_1") (pintype "power_in"))
      (node (ref "U12") (pin "1") (pinfunction "VCCA_1") (pintype "power_in"))
      (node (ref "U13") (pin "1") (pinfunction "VCCA_1") (pintype "power_in"))
      (node (ref "U14") (pin "1") (pinfunction "VCCA_1") (pintype "power_in"))
      (node (ref "U15") (pin "1") (pinfunction "VCCA_1") (pintype "power_in"))
    )
    (net (code "175") (name "5V_VME") (class "Default")
      (node (ref "C64") (pin "2") (pinfunction "2_2") (pintype "passive"))
      (node (ref "C65") (pin "2") (pinfunction "2_2") (pintype "passive"))
      (node (ref "C66") (pin "2") (pinfunction "2_2") (pintype "passive"))
      (node (ref "C67") (pin "2") (pinfunction "2_2") (pintype "passive"))
      (node (ref "C68") (pin "2") (pinfunction "2_2") (pintype "passive"))
      (node (ref "P2") (pin "A32") (pinfunction "A32_A32") (pintype "passive"))
      (node (ref "P2") (pin "B32") (pinfunction "B32_B32") (pintype "passive"))
      (node (ref "P2") (pin "C32") (pinfunction "C32_C32") (pintype "passive"))
      (node (ref "P3") (pin "B1") (pinfunction "B1_B1") (pintype "passive"))
      (node (ref "P3") (pin "B13") (pinfunction "B13_B13") (pintype "passive"))
      (node (ref "P3") (pin "B32") (pinfunction "B32_B32") (pintype "passive"))
      (node (ref "U1") (pin "23") (pinfunction "VCCB_23") (pintype "power_in"))
      (node (ref "U1") (pin "24") (pinfunction "VCCB_24") (pintype "power_in"))
      (node (ref "U10") (pin "23") (pinfunction "VCCB_23") (pintype "power_in"))
      (node (ref "U10") (pin "24") (pinfunction "VCCB_24") (pintype "power_in"))
      (node (ref "U11") (pin "23") (pinfunction "VCCB_23") (pintype "power_in"))
      (node (ref "U11") (pin "24") (pinfunction "VCCB_24") (pintype "power_in"))
      (node (ref "U12") (pin "23") (pinfunction "VCCB_23") (pintype "power_in"))
      (node (ref "U12") (pin "24") (pinfunction "VCCB_24") (pintype "power_in"))
      (node (ref "U13") (pin "23") (pinfunction "VCCB_23") (pintype "power_in"))
      (node (ref "U13") (pin "24") (pinfunction "VCCB_24") (pintype "power_in"))
      (node (ref "U14") (pin "23") (pinfunction "VCCB_23") (pintype "power_in"))
      (node (ref "U14") (pin "24") (pinfunction "VCCB_24") (pintype "power_in"))
      (node (ref "U15") (pin "23") (pinfunction "VCCB_23") (pintype "power_in"))
      (node (ref "U15") (pin "24") (pinfunction "VCCB_24") (pintype "power_in"))
    )
    (net (code "176") (name "GND") (class "Default")
      (node (ref "C64") (pin "1") (pinfunction "1_1") (pintype "passive"))
      (node (ref "C65") (pin "1") (pinfunction "1_1") (pintype "passive"))
      (node (ref "C66") (pin "1") (pinfunction "1_1") (pintype "passive"))
      (node (ref "C67") (pin "1") (pinfunction "1_1") (pintype "passive"))
      (node (ref "C68") (pin "1") (pinfunction "1_1") (pintype "passive"))
      (node (ref "C69") (pin "1") (pinfunction "1_1") (pintype "passive"))
      (node (ref "C70") (pin "1") (pinfunction "1_1") (pintype "passive"))
      (node (ref "C71") (pin "1") (pinfunction "1_1") (pintype "passive"))
      (node (ref "C72") (pin "1") (pinfunction "1_1") (pintype "passive"))
      (node (ref "C73") (pin "1") (pinfunction "1_1") (pintype "passive"))
      (node (ref "P2") (pin "A11") (pinfunction "A11_A11") (pintype "passive"))
      (node (ref "P2") (pin "A15") (pinfunction "A15_A15") (pintype "passive"))
      (node (ref "P2") (pin "A17") (pinfunction "A17_A17") (pintype "passive"))
      (node (ref "P2") (pin "A19") (pinfunction "A19_A19") (pintype "passive"))
      (node (ref "P2") (pin "A9") (pinfunction "A9_A9") (pintype "passive"))
      (node (ref "P2") (pin "B20") (pinfunction "B20_B20") (pintype "passive"))
      (node (ref "P2") (pin "B23") (pinfunction "B23_B23") (pintype "passive"))
      (node (ref "P2") (pin "C9") (pinfunction "C9_C9") (pintype "passive"))
      (node (ref "P3") (pin "B12") (pinfunction "B12_B12") (pintype "passive"))
      (node (ref "P3") (pin "B2") (pinfunction "B2_B2") (pintype "passive"))
      (node (ref "P3") (pin "B22") (pinfunction "B22_B22") (pintype "passive"))
      (node (ref "P3") (pin "B31") (pinfunction "B31_B31") (pintype "passive"))
      (node (ref "R74") (pin "3") (pinfunction "3_3") (pintype "passive"))
      (node (ref "R74") (pin "4") (pinfunction "4_4") (pintype "passive"))
      (node (ref "U1") (pin "11") (pinfunction "GND_11") (pintype "power_in"))
      (node (ref "U1") (pin "12") (pinfunction "GND_12") (pintype "power_in"))
      (node (ref "U1") (pin "13") (pinfunction "GND_13") (pintype "power_in"))
      (node (ref "U10") (pin "11") (pinfunction "GND_11") (pintype "power_in"))
      (node (ref "U10") (pin "12") (pinfunction "GND_12") (pintype "power_in"))
      (node (ref "U10") (pin "13") (pinfunction "GND_13") (pintype "power_in"))
      (node (ref "U11") (pin "11") (pinfunction "GND_11") (pintype "power_in"))
      (node (ref "U11") (pin "12") (pinfunction "GND_12") (pintype "power_in"))
      (node (ref "U11") (pin "13") (pinfunction "GND_13") (pintype "power_in"))
      (node (ref "U12") (pin "11") (pinfunction "GND_11") (pintype "power_in"))
      (node (ref "U12") (pin "12") (pinfunction "GND_12") (pintype "power_in"))
      (node (ref "U12") (pin "13") (pinfunction "GND_13") (pintype "power_in"))
      (node (ref "U13") (pin "11") (pinfunction "GND_11") (pintype "power_in"))
      (node (ref "U13") (pin "12") (pinfunction "GND_12") (pintype "power_in"))
      (node (ref "U13") (pin "13") (pinfunction "GND_13") (pintype "power_in"))
      (node (ref "U14") (pin "11") (pinfunction "GND_11") (pintype "power_in"))
      (node (ref "U14") (pin "12") (pinfunction "GND_12") (pintype "power_in"))
      (node (ref "U14") (pin "13") (pinfunction "GND_13") (pintype "power_in"))
      (node (ref "U15") (pin "11") (pinfunction "GND_11") (pintype "power_in"))
      (node (ref "U15") (pin "12") (pinfunction "GND_12") (pintype "power_in"))
      (node (ref "U15") (pin "13") (pinfunction "GND_13") (pintype "power_in"))
    )
    (net (code "177") (name "Net-(U1-A1)") (class "Default")
      (node (ref "R32") (pin "8") (pinfunction "8_8") (pintype "passive"))
      (node (ref "U1") (pin "3") (pinfunction "A1_3") (pintype "bidirectional"))
    )
    (net (code "178") (name "Net-(U1-A2)") (class "Default")
      (node (ref "R32") (pin "7") (pinfunction "7_7") (pintype "passive"))
      (node (ref "U1") (pin "4") (pinfunction "A2_4") (pintype "bidirectional"))
    )
    (net (code "179") (name "Net-(U1-A3)") (class "Default")
      (node (ref "R32") (pin "6") (pinfunction "6_6") (pintype "passive"))
      (node (ref "U1") (pin "5") (pinfunction "A3_5") (pintype "bidirectional"))
    )
    (net (code "180") (name "Net-(U1-A4)") (class "Default")
      (node (ref "R32") (pin "5") (pinfunction "5_5") (pintype "passive"))
      (node (ref "U1") (pin "6") (pinfunction "A4_6") (pintype "bidirectional"))
    )
    (net (code "181") (name "Net-(U1-A5)") (class "Default")
      (node (ref "R35") (pin "8") (pinfunction "8_8") (pintype "passive"))
      (node (ref "U1") (pin "7") (pinfunction "A5_7") (pintype "bidirectional"))
    )
    (net (code "182") (name "Net-(U1-A6)") (class "Default")
      (node (ref "R35") (pin "7") (pinfunction "7_7") (pintype "passive"))
      (node (ref "U1") (pin "8") (pinfunction "A6_8") (pintype "bidirectional"))
    )
    (net (code "183") (name "Net-(U1-A7)") (class "Default")
      (node (ref "R35") (pin "6") (pinfunction "6_6") (pintype "passive"))
      (node (ref "U1") (pin "9") (pinfunction "A7_9") (pintype "bidirectional"))
    )
    (net (code "184") (name "Net-(U1-A8)") (class "Default")
      (node (ref "R35") (pin "5") (pinfunction "5_5") (pintype "passive"))
      (node (ref "U1") (pin "10") (pinfunction "A8_10") (pintype "bidirectional"))
    )
    (net (code "185") (name "Net-(U10-A1)") (class "Default")
      (node (ref "R33") (pin "8") (pinfunction "8_8") (pintype "passive"))
      (node (ref "U10") (pin "3") (pinfunction "A1_3") (pintype "bidirectional"))
    )
    (net (code "186") (name "Net-(U10-A2)") (class "Default")
      (node (ref "R33") (pin "7") (pinfunction "7_7") (pintype "passive"))
      (node (ref "U10") (pin "4") (pinfunction "A2_4") (pintype "bidirectional"))
    )
    (net (code "187") (name "Net-(U10-A3)") (class "Default")
      (node (ref "R33") (pin "6") (pinfunction "6_6") (pintype "passive"))
      (node (ref "U10") (pin "5") (pinfunction "A3_5") (pintype "bidirectional"))
    )
    (net (code "188") (name "Net-(U10-A4)") (class "Default")
      (node (ref "R33") (pin "5") (pinfunction "5_5") (pintype "passive"))
      (node (ref "U10") (pin "6") (pinfunction "A4_6") (pintype "bidirectional"))
    )
    (net (code "189") (name "Net-(U10-A5)") (class "Default")
      (node (ref "R36") (pin "8") (pinfunction "8_8") (pintype "passive"))
      (node (ref "U10") (pin "7") (pinfunction "A5_7") (pintype "bidirectional"))
    )
    (net (code "190") (name "Net-(U10-A6)") (class "Default")
      (node (ref "R36") (pin "7") (pinfunction "7_7") (pintype "passive"))
      (node (ref "U10") (pin "8") (pinfunction "A6_8") (pintype "bidirectional"))
    )
    (net (code "191") (name "Net-(U10-A7)") (class "Default")
      (node (ref "R36") (pin "6") (pinfunction "6_6") (pintype "passive"))
      (node (ref "U10") (pin "9") (pinfunction "A7_9") (pintype "bidirectional"))
    )
    (net (code "192") (name "Net-(U10-A8)") (class "Default")
      (node (ref "R36") (pin "5") (pinfunction "5_5") (pintype "passive"))
      (node (ref "U10") (pin "10") (pinfunction "A8_10") (pintype "bidirectional"))
    )
    (net (code "193") (name "Net-(U11-A1)") (class "Default")
      (node (ref "R37") (pin "8") (pinfunction "8_8") (pintype "passive"))
      (node (ref "U11") (pin "3") (pinfunction "A1_3") (pintype "bidirectional"))
    )
    (net (code "194") (name "Net-(U11-A2)") (class "Default")
      (node (ref "R37") (pin "7") (pinfunction "7_7") (pintype "passive"))
      (node (ref "U11") (pin "4") (pinfunction "A2_4") (pintype "bidirectional"))
    )
    (net (code "195") (name "Net-(U11-A3)") (class "Default")
      (node (ref "R37") (pin "6") (pinfunction "6_6") (pintype "passive"))
      (node (ref "U11") (pin "5") (pinfunction "A3_5") (pintype "bidirectional"))
    )
    (net (code "196") (name "Net-(U11-A4)") (class "Default")
      (node (ref "R37") (pin "5") (pinfunction "5_5") (pintype "passive"))
      (node (ref "U11") (pin "6") (pinfunction "A4_6") (pintype "bidirectional"))
    )
    (net (code "197") (name "Net-(U11-A5)") (class "Default")
      (node (ref "R69") (pin "8") (pinfunction "8_8") (pintype "passive"))
      (node (ref "U11") (pin "7") (pinfunction "A5_7") (pintype "bidirectional"))
    )
    (net (code "198") (name "Net-(U11-A6)") (class "Default")
      (node (ref "R69") (pin "7") (pinfunction "7_7") (pintype "passive"))
      (node (ref "U11") (pin "8") (pinfunction "A6_8") (pintype "bidirectional"))
    )
    (net (code "199") (name "Net-(U11-A7)") (class "Default")
      (node (ref "R69") (pin "6") (pinfunction "6_6") (pintype "passive"))
      (node (ref "U11") (pin "9") (pinfunction "A7_9") (pintype "bidirectional"))
    )
    (net (code "200") (name "Net-(U11-A8)") (class "Default")
      (node (ref "R69") (pin "5") (pinfunction "5_5") (pintype "passive"))
      (node (ref "U11") (pin "10") (pinfunction "A8_10") (pintype "bidirectional"))
    )
    (net (code "201") (name "Net-(U12-A1)") (class "Default")
      (node (ref "R38") (pin "8") (pinfunction "8_8") (pintype "passive"))
      (node (ref "U12") (pin "3") (pinfunction "A1_3") (pintype "bidirectional"))
    )
    (net (code "202") (name "Net-(U12-A2)") (class "Default")
      (node (ref "R38") (pin "7") (pinfunction "7_7") (pintype "passive"))
      (node (ref "U12") (pin "4") (pinfunction "A2_4") (pintype "bidirectional"))
    )
    (net (code "203") (name "Net-(U12-A3)") (class "Default")
      (node (ref "R38") (pin "6") (pinfunction "6_6") (pintype "passive"))
      (node (ref "U12") (pin "5") (pinfunction "A3_5") (pintype "bidirectional"))
    )
    (net (code "204") (name "Net-(U12-A4)") (class "Default")
      (node (ref "R38") (pin "5") (pinfunction "5_5") (pintype "passive"))
      (node (ref "U12") (pin "6") (pinfunction "A4_6") (pintype "bidirectional"))
    )
    (net (code "205") (name "Net-(U12-A5)") (class "Default")
      (node (ref "R70") (pin "8") (pinfunction "8_8") (pintype "passive"))
      (node (ref "U12") (pin "7") (pinfunction "A5_7") (pintype "bidirectional"))
    )
    (net (code "206") (name "Net-(U12-A6)") (class "Default")
      (node (ref "R70") (pin "7") (pinfunction "7_7") (pintype "passive"))
      (node (ref "U12") (pin "8") (pinfunction "A6_8") (pintype "bidirectional"))
    )
    (net (code "207") (name "Net-(U12-A7)") (class "Default")
      (node (ref "R70") (pin "6") (pinfunction "6_6") (pintype "passive"))
      (node (ref "U12") (pin "9") (pinfunction "A7_9") (pintype "bidirectional"))
    )
    (net (code "208") (name "Net-(U12-A8)") (class "Default")
      (node (ref "R70") (pin "5") (pinfunction "5_5") (pintype "passive"))
      (node (ref "U12") (pin "10") (pinfunction "A8_10") (pintype "bidirectional"))
    )
    (net (code "209") (name "Net-(U13-A1)") (class "Default")
      (node (ref "R39") (pin "8") (pinfunction "8_8") (pintype "passive"))
      (node (ref "U13") (pin "3") (pinfunction "A1_3") (pintype "bidirectional"))
    )
    (net (code "210") (name "Net-(U13-A2)") (class "Default")
      (node (ref "R39") (pin "7") (pinfunction "7_7") (pintype "passive"))
      (node (ref "U13") (pin "4") (pinfunction "A2_4") (pintype "bidirectional"))
    )
    (net (code "211") (name "Net-(U13-A3)") (class "Default")
      (node (ref "R39") (pin "6") (pinfunction "6_6") (pintype "passive"))
      (node (ref "U13") (pin "5") (pinfunction "A3_5") (pintype "bidirectional"))
    )
    (net (code "212") (name "Net-(U13-A4)") (class "Default")
      (node (ref "R39") (pin "5") (pinfunction "5_5") (pintype "passive"))
      (node (ref "U13") (pin "6") (pinfunction "A4_6") (pintype "bidirectional"))
    )
    (net (code "213") (name "Net-(U13-A5)") (class "Default")
      (node (ref "R71") (pin "8") (pinfunction "8_8") (pintype "passive"))
      (node (ref "U13") (pin "7") (pinfunction "A5_7") (pintype "bidirectional"))
    )
    (net (code "214") (name "Net-(U13-A6)") (class "Default")
      (node (ref "R71") (pin "7") (pinfunction "7_7") (pintype "passive"))
      (node (ref "U13") (pin "8") (pinfunction "A6_8") (pintype "bidirectional"))
    )
    (net (code "215") (name "Net-(U13-A7)") (class "Default")
      (node (ref "R71") (pin "6") (pinfunction "6_6") (pintype "passive"))
      (node (ref "U13") (pin "9") (pinfunction "A7_9") (pintype "bidirectional"))
    )
    (net (code "216") (name "Net-(U13-A8)") (class "Default")
      (node (ref "R71") (pin "5") (pinfunction "5_5") (pintype "passive"))
      (node (ref "U13") (pin "10") (pinfunction "A8_10") (pintype "bidirectional"))
    )
    (net (code "217") (name "Net-(U14-A1)") (class "Default")
      (node (ref "R73") (pin "8") (pinfunction "8_8") (pintype "passive"))
      (node (ref "U14") (pin "3") (pinfunction "A1_3") (pintype "bidirectional"))
    )
    (net (code "218") (name "Net-(U14-A2)") (class "Default")
      (node (ref "R73") (pin "7") (pinfunction "7_7") (pintype "passive"))
      (node (ref "U14") (pin "4") (pinfunction "A2_4") (pintype "bidirectional"))
    )
    (net (code "219") (name "Net-(U14-A3)") (class "Default")
      (node (ref "R73") (pin "6") (pinfunction "6_6") (pintype "passive"))
      (node (ref "U14") (pin "5") (pinfunction "A3_5") (pintype "bidirectional"))
    )
    (net (code "220") (name "Net-(U14-A4)") (class "Default")
      (node (ref "R73") (pin "5") (pinfunction "5_5") (pintype "passive"))
      (node (ref "U14") (pin "6") (pinfunction "A4_6") (pintype "bidirectional"))
    )
    (net (code "221") (name "Net-(U14-A5)") (class "Default")
      (node (ref "R74") (pin "8") (pinfunction "8_8") (pintype "passive"))
      (node (ref "U14") (pin "7") (pinfunction "A5_7") (pintype "bidirectional"))
    )
    (net (code "222") (name "Net-(U14-A6)") (class "Default")
      (node (ref "R74") (pin "7") (pinfunction "7_7") (pintype "passive"))
      (node (ref "U14") (pin "8") (pinfunction "A6_8") (pintype "bidirectional"))
    )
    (net (code "223") (name "Net-(U14-A7)") (class "Default")
      (node (ref "R74") (pin "6") (pinfunction "6_6") (pintype "passive"))
      (node (ref "U14") (pin "9") (pinfunction "A7_9") (pintype "bidirectional"))
    )
    (net (code "224") (name "Net-(U14-A8)") (class "Default")
      (node (ref "R74") (pin "5") (pinfunction "5_5") (pintype "passive"))
      (node (ref "U14") (pin "10") (pinfunction "A8_10") (pintype "bidirectional"))
    )
    (net (code "225") (name "Net-(U15-A1)") (class "Default")
      (node (ref "R75") (pin "8") (pinfunction "8_8") (pintype "passive"))
      (node (ref "U15") (pin "3") (pinfunction "A1_3") (pintype "bidirectional"))
    )
    (net (code "226") (name "Net-(U15-A2)") (class "Default")
      (node (ref "R75") (pin "7") (pinfunction "7_7") (pintype "passive"))
      (node (ref "U15") (pin "4") (pinfunction "A2_4") (pintype "bidirectional"))
    )
    (net (code "227") (name "Net-(U15-A3)") (class "Default")
      (node (ref "R75") (pin "6") (pinfunction "6_6") (pintype "passive"))
      (node (ref "U15") (pin "5") (pinfunction "A3_5") (pintype "bidirectional"))
    )
    (net (code "228") (name "Net-(U15-A4)") (class "Default")
      (node (ref "R75") (pin "5") (pinfunction "5_5") (pintype "passive"))
      (node (ref "U15") (pin "6") (pinfunction "A4_6") (pintype "bidirectional"))
    )
    (net (code "229") (name "Net-(U15-A5)") (class "Default")
      (node (ref "R76") (pin "8") (pinfunction "8_8") (pintype "passive"))
      (node (ref "U15") (pin "7") (pinfunction "A5_7") (pintype "bidirectional"))
    )
    (net (code "230") (name "Net-(U15-A6)") (class "Default")
      (node (ref "R76") (pin "7") (pinfunction "7_7") (pintype "passive"))
      (node (ref "U15") (pin "8") (pinfunction "A6_8") (pintype "bidirectional"))
    )
    (net (code "231") (name "Net-(U15-A7)") (class "Default")
      (node (ref "R76") (pin "6") (pinfunction "6_6") (pintype "passive"))
      (node (ref "U15") (pin "9") (pinfunction "A7_9") (pintype "bidirectional"))
    )
    (net (code "232") (name "Net-(U15-A8)") (class "Default")
      (node (ref "R76") (pin "5") (pinfunction "5_5") (pintype "passive"))
      (node (ref "U15") (pin "10") (pinfunction "A8_10") (pintype "bidirectional"))
    )
    (net (code "233") (name "unconnected-(P2-PadB21)") (class "Default")
      (node (ref "P2") (pin "B21") (pinfunction "B21_B21") (pintype "passive"))
    )
    (net (code "234") (name "unconnected-(P2-PadB22)") (class "Default")
      (node (ref "P2") (pin "B22") (pinfunction "B22_B22") (pintype "passive"))
    )
    (net (code "235") (name "unconnected-(P2-PadB31)") (class "Default")
      (node (ref "P2") (pin "B31") (pinfunction "B31_B31") (pintype "passive"))
    )
    (net (code "236") (name "unconnected-(P3-PadA1)") (class "Default")
      (node (ref "P3") (pin "A1") (pinfunction "A1_A1") (pintype "passive"))
    )
    (net (code "237") (name "unconnected-(P3-PadA2)") (class "Default")
      (node (ref "P3") (pin "A2") (pinfunction "A2_A2") (pintype "passive"))
    )
    (net (code "238") (name "unconnected-(P3-PadA3)") (class "Default")
      (node (ref "P3") (pin "A3") (pinfunction "A3_A3") (pintype "passive"))
    )
    (net (code "239") (name "unconnected-(P3-PadA4)") (class "Default")
      (node (ref "P3") (pin "A4") (pinfunction "A4_A4") (pintype "passive"))
    )
    (net (code "240") (name "unconnected-(P3-PadA5)") (class "Default")
      (node (ref "P3") (pin "A5") (pinfunction "A5_A5") (pintype "passive"))
    )
    (net (code "241") (name "unconnected-(P3-PadA6)") (class "Default")
      (node (ref "P3") (pin "A6") (pinfunction "A6_A6") (pintype "passive"))
    )
    (net (code "242") (name "unconnected-(P3-PadA7)") (class "Default")
      (node (ref "P3") (pin "A7") (pinfunction "A7_A7") (pintype "passive"))
    )
    (net (code "243") (name "unconnected-(P3-PadA8)") (class "Default")
      (node (ref "P3") (pin "A8") (pinfunction "A8_A8") (pintype "passive"))
    )
    (net (code "244") (name "unconnected-(P3-PadA9)") (class "Default")
      (node (ref "P3") (pin "A9") (pinfunction "A9_A9") (pintype "passive"))
    )
    (net (code "245") (name "unconnected-(P3-PadA10)") (class "Default")
      (node (ref "P3") (pin "A10") (pinfunction "A10_A10") (pintype "passive"))
    )
    (net (code "246") (name "unconnected-(P3-PadA11)") (class "Default")
      (node (ref "P3") (pin "A11") (pinfunction "A11_A11") (pintype "passive"))
    )
    (net (code "247") (name "unconnected-(P3-PadA12)") (class "Default")
      (node (ref "P3") (pin "A12") (pinfunction "A12_A12") (pintype "passive"))
    )
    (net (code "248") (name "unconnected-(P3-PadA13)") (class "Default")
      (node (ref "P3") (pin "A13") (pinfunction "A13_A13") (pintype "passive"))
    )
    (net (code "249") (name "unconnected-(P3-PadA14)") (class "Default")
      (node (ref "P3") (pin "A14") (pinfunction "A14_A14") (pintype "passive"))
    )
    (net (code "250") (name "unconnected-(P3-PadA15)") (class "Default")
      (node (ref "P3") (pin "A15") (pinfunction "A15_A15") (pintype "passive"))
    )
    (net (code "251") (name "unconnected-(P3-PadA16)") (class "Default")
      (node (ref "P3") (pin "A16") (pinfunction "A16_A16") (pintype "passive"))
    )
    (net (code "252") (name "unconnected-(P3-PadA17)") (class "Default")
      (node (ref "P3") (pin "A17") (pinfunction "A17_A17") (pintype "passive"))
    )
    (net (code "253") (name "unconnected-(P3-PadA18)") (class "Default")
      (node (ref "P3") (pin "A18") (pinfunction "A18_A18") (pintype "passive"))
    )
    (net (code "254") (name "unconnected-(P3-PadA19)") (class "Default")
      (node (ref "P3") (pin "A19") (pinfunction "A19_A19") (pintype "passive"))
    )
    (net (code "255") (name "unconnected-(P3-PadA20)") (class "Default")
      (node (ref "P3") (pin "A20") (pinfunction "A20_A20") (pintype "passive"))
    )
    (net (code "256") (name "unconnected-(P3-PadA21)") (class "Default")
      (node (ref "P3") (pin "A21") (pinfunction "A21_A21") (pintype "passive"))
    )
    (net (code "257") (name "unconnected-(P3-PadA22)") (class "Default")
      (node (ref "P3") (pin "A22") (pinfunction "A22_A22") (pintype "passive"))
    )
    (net (code "258") (name "unconnected-(P3-PadA23)") (class "Default")
      (node (ref "P3") (pin "A23") (pinfunction "A23_A23") (pintype "passive"))
    )
    (net (code "259") (name "unconnected-(P3-PadA24)") (class "Default")
      (node (ref "P3") (pin "A24") (pinfunction "A24_A24") (pintype "passive"))
    )
    (net (code "260") (name "unconnected-(P3-PadA25)") (class "Default")
      (node (ref "P3") (pin "A25") (pinfunction "A25_A25") (pintype "passive"))
    )
    (net (code "261") (name "unconnected-(P3-PadA26)") (class "Default")
      (node (ref "P3") (pin "A26") (pinfunction "A26_A26") (pintype "passive"))
    )
    (net (code "262") (name "unconnected-(P3-PadA27)") (class "Default")
      (node (ref "P3") (pin "A27") (pinfunction "A27_A27") (pintype "passive"))
    )
    (net (code "263") (name "unconnected-(P3-PadA28)") (class "Default")
      (node (ref "P3") (pin "A28") (pinfunction "A28_A28") (pintype "passive"))
    )
    (net (code "264") (name "unconnected-(P3-PadA29)") (class "Default")
      (node (ref "P3") (pin "A29") (pinfunction "A29_A29") (pintype "passive"))
    )
    (net (code "265") (name "unconnected-(P3-PadA30)") (class "Default")
      (node (ref "P3") (pin "A30") (pinfunction "A30_A30") (pintype "passive"))
    )
    (net (code "266") (name "unconnected-(P3-PadA31)") (class "Default")
      (node (ref "P3") (pin "A31") (pinfunction "A31_A31") (pintype "passive"))
    )
    (net (code "267") (name "unconnected-(P3-PadA32)") (class "Default")
      (node (ref "P3") (pin "A32") (pinfunction "A32_A32") (pintype "passive"))
    )
    (net (code "268") (name "unconnected-(P3-PadB3)") (class "Default")
      (node (ref "P3") (pin "B3") (pinfunction "B3_B3") (pintype "passive"))
    )
    (net (code "269") (name "unconnected-(P3-PadC1)") (class "Default")
      (node (ref "P3") (pin "C1") (pinfunction "C1_C1") (pintype "passive"))
    )
    (net (code "270") (name "unconnected-(P3-PadC2)") (class "Default")
      (node (ref "P3") (pin "C2") (pinfunction "C2_C2") (pintype "passive"))
    )
    (net (code "271") (name "unconnected-(P3-PadC3)") (class "Default")
      (node (ref "P3") (pin "C3") (pinfunction "C3_C3") (pintype "passive"))
    )
    (net (code "272") (name "unconnected-(P3-PadC4)") (class "Default")
      (node (ref "P3") (pin "C4") (pinfunction "C4_C4") (pintype "passive"))
    )
    (net (code "273") (name "unconnected-(P3-PadC5)") (class "Default")
      (node (ref "P3") (pin "C5") (pinfunction "C5_C5") (pintype "passive"))
    )
    (net (code "274") (name "unconnected-(P3-PadC6)") (class "Default")
      (node (ref "P3") (pin "C6") (pinfunction "C6_C6") (pintype "passive"))
    )
    (net (code "275") (name "unconnected-(P3-PadC7)") (class "Default")
      (node (ref "P3") (pin "C7") (pinfunction "C7_C7") (pintype "passive"))
    )
    (net (code "276") (name "unconnected-(P3-PadC8)") (class "Default")
      (node (ref "P3") (pin "C8") (pinfunction "C8_C8") (pintype "passive"))
    )
    (net (code "277") (name "unconnected-(P3-PadC9)") (class "Default")
      (node (ref "P3") (pin "C9") (pinfunction "C9_C9") (pintype "passive"))
    )
    (net (code "278") (name "unconnected-(P3-PadC10)") (class "Default")
      (node (ref "P3") (pin "C10") (pinfunction "C10_C10") (pintype "passive"))
    )
    (net (code "279") (name "unconnected-(P3-PadC11)") (class "Default")
      (node (ref "P3") (pin "C11") (pinfunction "C11_C11") (pintype "passive"))
    )
    (net (code "280") (name "unconnected-(P3-PadC12)") (class "Default")
      (node (ref "P3") (pin "C12") (pinfunction "C12_C12") (pintype "passive"))
    )
    (net (code "281") (name "unconnected-(P3-PadC13)") (class "Default")
      (node (ref "P3") (pin "C13") (pinfunction "C13_C13") (pintype "passive"))
    )
    (net (code "282") (name "unconnected-(P3-PadC14)") (class "Default")
      (node (ref "P3") (pin "C14") (pinfunction "C14_C14") (pintype "passive"))
    )
    (net (code "283") (name "unconnected-(P3-PadC15)") (class "Default")
      (node (ref "P3") (pin "C15") (pinfunction "C15_C15") (pintype "passive"))
    )
    (net (code "284") (name "unconnected-(P3-PadC16)") (class "Default")
      (node (ref "P3") (pin "C16") (pinfunction "C16_C16") (pintype "passive"))
    )
    (net (code "285") (name "unconnected-(P3-PadC17)") (class "Default")
      (node (ref "P3") (pin "C17") (pinfunction "C17_C17") (pintype "passive"))
    )
    (net (code "286") (name "unconnected-(P3-PadC18)") (class "Default")
      (node (ref "P3") (pin "C18") (pinfunction "C18_C18") (pintype "passive"))
    )
    (net (code "287") (name "unconnected-(P3-PadC19)") (class "Default")
      (node (ref "P3") (pin "C19") (pinfunction "C19_C19") (pintype "passive"))
    )
    (net (code "288") (name "unconnected-(P3-PadC20)") (class "Default")
      (node (ref "P3") (pin "C20") (pinfunction "C20_C20") (pintype "passive"))
    )
    (net (code "289") (name "unconnected-(P3-PadC21)") (class "Default")
      (node (ref "P3") (pin "C21") (pinfunction "C21_C21") (pintype "passive"))
    )
    (net (code "290") (name "unconnected-(P3-PadC22)") (class "Default")
      (node (ref "P3") (pin "C22") (pinfunction "C22_C22") (pintype "passive"))
    )
    (net (code "291") (name "unconnected-(P3-PadC23)") (class "Default")
      (node (ref "P3") (pin "C23") (pinfunction "C23_C23") (pintype "passive"))
    )
    (net (code "292") (name "unconnected-(P3-PadC24)") (class "Default")
      (node (ref "P3") (pin "C24") (pinfunction "C24_C24") (pintype "passive"))
    )
    (net (code "293") (name "unconnected-(P3-PadC25)") (class "Default")
      (node (ref "P3") (pin "C25") (pinfunction "C25_C25") (pintype "passive"))
    )
    (net (code "294") (name "unconnected-(P3-PadC26)") (class "Default")
      (node (ref "P3") (pin "C26") (pinfunction "C26_C26") (pintype "passive"))
    )
    (net (code "295") (name "unconnected-(P3-PadC27)") (class "Default")
      (node (ref "P3") (pin "C27") (pinfunction "C27_C27") (pintype "passive"))
    )
    (net (code "296") (name "unconnected-(P3-PadC28)") (class "Default")
      (node (ref "P3") (pin "C28") (pinfunction "C28_C28") (pintype "passive"))
    )
    (net (code "297") (name "unconnected-(P3-PadC29)") (class "Default")
      (node (ref "P3") (pin "C29") (pinfunction "C29_C29") (pintype "passive"))
    )
    (net (code "298") (name "unconnected-(P3-PadC30)") (class "Default")
      (node (ref "P3") (pin "C30") (pinfunction "C30_C30") (pintype "passive"))
    )
    (net (code "299") (name "unconnected-(P3-PadC31)") (class "Default")
      (node (ref "P3") (pin "C31") (pinfunction "C31_C31") (pintype "passive"))
    )
    (net (code "300") (name "unconnected-(P3-PadC32)") (class "Default")
      (node (ref "P3") (pin "C32") (pinfunction "C32_C32") (pintype "passive"))
    )
    (net (code "301") (name "unconnected-(R37-Pad1)") (class "Default")
      (node (ref "R37") (pin "1") (pinfunction "1_1") (pintype "passive"))
    )
    (net (code "302") (name "unconnected-(R76-Pad3)") (class "Default")
      (node (ref "R76") (pin "3") (pinfunction "3_3") (pintype "passive"))
    )
    (net (code "303") (name "unconnected-(R76-Pad4)") (class "Default")
      (node (ref "R76") (pin "4") (pinfunction "4_4") (pintype "passive"))
    )
    (net (code "304") (name "unconnected-(U11-B1-Pad21)") (class "Default")
      (node (ref "U11") (pin "21") (pinfunction "B1_21") (pintype "bidirectional"))
    )
    (net (code "305") (name "unconnected-(U14-B7-Pad15)") (class "Default")
      (node (ref "U14") (pin "15") (pinfunction "B7_15") (pintype "bidirectional"))
    )
    (net (code "306") (name "unconnected-(U14-B8-Pad14)") (class "Default")
      (node (ref "U14") (pin "14") (pinfunction "B8_14") (pintype "bidirectional"))
    )
    (net (code "307") (name "unconnected-(U15-B7-Pad15)") (class "Default")
      (node (ref "U15") (pin "15") (pinfunction "B7_15") (pintype "bidirectional"))
    )
    (net (code "308") (name "unconnected-(U15-B8-Pad14)") (class "Default")
      (node (ref "U15") (pin "14") (pinfunction "B8_14") (pintype "bidirectional"))
    )
  )
)
